# Power_Management.net
KiCad netlist of a schematic drawn in Altium Designer
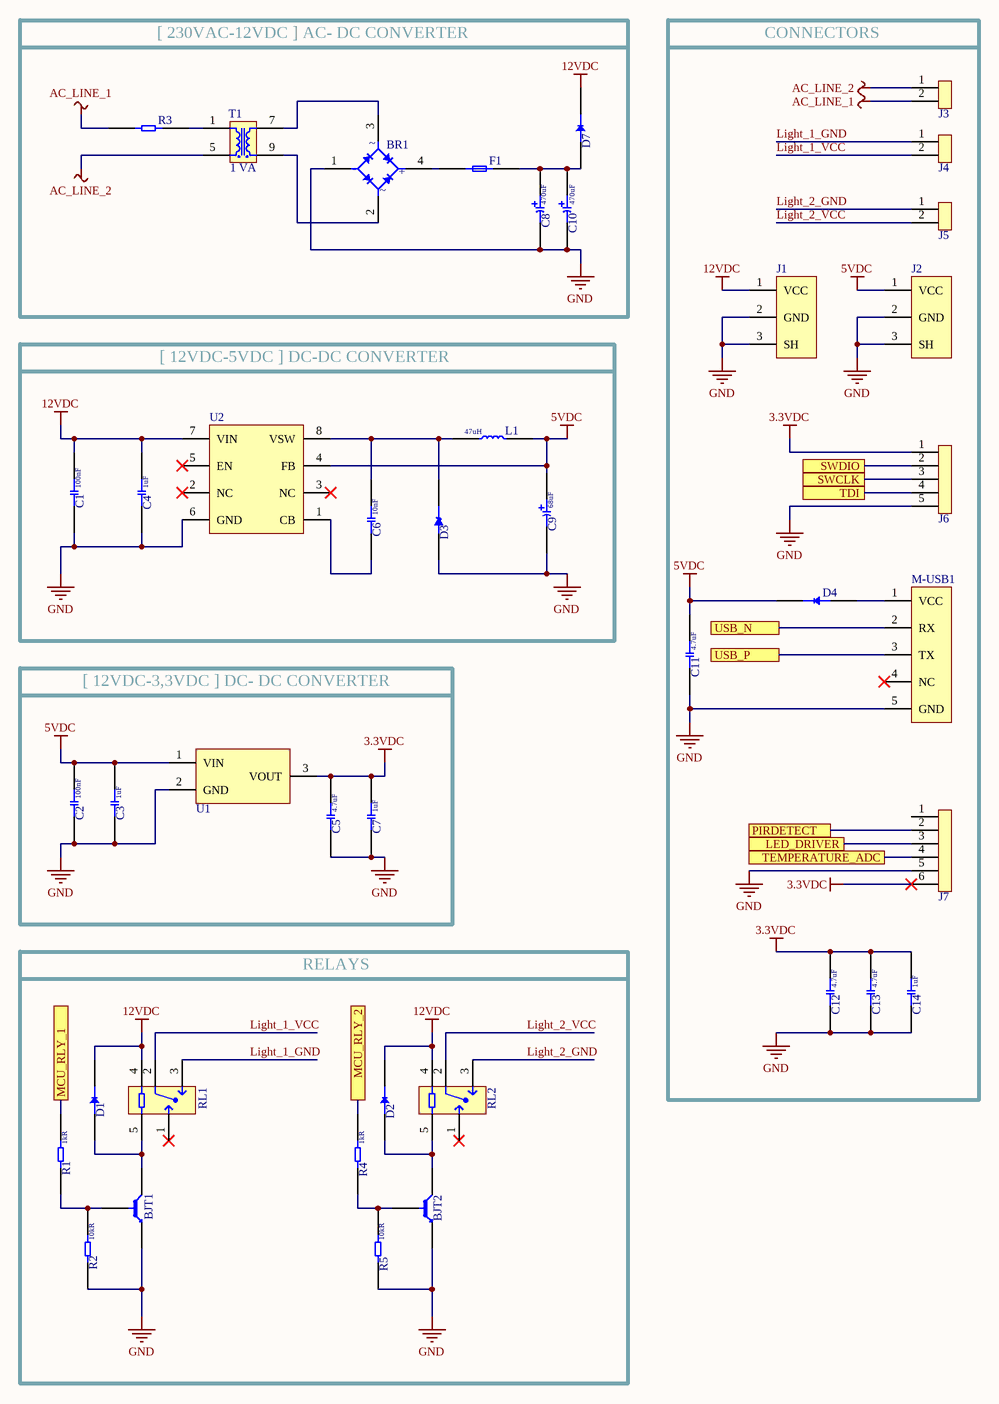
[diagram p0: Power Management.SchDoc]

(export (version "E")
  (design (tool "Eeschema 10.0.6"))
  (components
    (comp (ref "BJT1")
      (value "MMBT3904-7-F")
      (footprint "SOT-23F")
      (description "TRANS NPN 40V 0.2A SMD SOT23-3")
      (fields (field (name "MANUFACTURER") "Diodes Zetex") (field (name "DESIGNED BY") "M.C"))
      (libsource (lib "HedefPro_Library") (part "MMBT3904-7-F"))
    )
    (comp (ref "BJT2")
      (value "MMBT3904-7-F")
      (footprint "SOT-23F")
      (description "TRANS NPN 40V 0.2A SMD SOT23-3")
      (fields (field (name "MANUFACTURER") "Diodes Zetex") (field (name "DESIGNED BY") "M.C"))
      (libsource (lib "HedefPro_Library") (part "MMBT3904-7-F"))
    )
    (comp (ref "BR1")
      (value "DB105STR")
      (footprint "DB105STR")
      (description "BRIDGE RECT 1PHASE 600V 1A DB-S")
      (fields (field (name "MANUFACTURER") "Sangdest Microelectronics") (field (name "DESIGNED BY") "M.C"))
      (libsource (lib "HedefPro_Library") (part "DB105STR"))
    )
    (comp (ref "C1")
      (value "C0603C104K5RACTU")
      (footprint "CAP_0603")
      (description "Multilayer Ceramic Capacitors (MLCC) - SMD/SMT 50volts 0.1uF X7R 10%")
      (fields
        (field (name "MANUFACTURER") "KEMET")
        (field (name "TOLERANCE") "10%")
        (field (name "CAPACITANCE") "100nF")
        (field (name "DESIGNED BY") "M.C")
      )
      (libsource (lib "HedefPro_Library") (part "CAP 100nF 0603"))
    )
    (comp (ref "C2")
      (value "C0603C104K5RACTU")
      (footprint "CAP_0603")
      (description "Multilayer Ceramic Capacitors (MLCC) - SMD/SMT 50volts 0.1uF X7R 10%")
      (fields
        (field (name "MANUFACTURER") "KEMET")
        (field (name "TOLERANCE") "10%")
        (field (name "CAPACITANCE") "100nF")
        (field (name "DESIGNED BY") "M.C")
      )
      (libsource (lib "HedefPro_Library") (part "CAP 100nF 0603"))
    )
    (comp (ref "C3")
      (value "CL21B105KBFNNNE")
      (footprint "CAP_0805")
      (fields
        (field (name "MANUFACTURER") "Samsung")
        (field (name "TOLERANCE") "10%")
        (field (name "VOLTAGE") "50V")
        (field (name "CAPACITANCE") "1uF")
        (field (name "DESIGNED BY") "M.C")
      )
      (libsource (lib "HedefPro_Library") (part "CAP 1uF 0805"))
    )
    (comp (ref "C4")
      (value "CL21B105KBFNNNE")
      (footprint "CAP_0805")
      (fields
        (field (name "MANUFACTURER") "Samsung")
        (field (name "TOLERANCE") "10%")
        (field (name "VOLTAGE") "50V")
        (field (name "CAPACITANCE") "1uF")
        (field (name "DESIGNED BY") "M.C")
      )
      (libsource (lib "HedefPro_Library") (part "CAP 1uF 0805"))
    )
    (comp (ref "C5")
      (value "CL21A475KAQNNNE")
      (footprint "CAP_0805")
      (fields
        (field (name "MANUFACTURER") "Samsung")
        (field (name "TOLERANCE") "10%")
        (field (name "CAPACITANCE") "4.7uF")
        (field (name "DESIGNED BY") "M.C")
      )
      (libsource (lib "HedefPro_Library") (part "CAP 4.7uF 0805"))
    )
    (comp (ref "C6")
      (value "0603B103K500CT")
      (footprint "CAP_0603")
      (description "WALSIN - 0603B103K500CT - CAP, 0.01µF, 50V, 10%, X7R, 0603")
      (fields
        (field (name "MANUFACTURER") "Walsin Technologies")
        (field (name "TOLERANCE") "10%")
        (field (name "CAPACITANCE") "10nF")
        (field (name "DESIGNED BY") "M.C")
      )
      (libsource (lib "HedefPro_Library") (part "CAP 10nF 0603"))
    )
    (comp (ref "C7")
      (value "CL21B105KBFNNNE")
      (footprint "CAP_0805")
      (fields
        (field (name "MANUFACTURER") "Samsung")
        (field (name "TOLERANCE") "10%")
        (field (name "VOLTAGE") "50V")
        (field (name "CAPACITANCE") "1uF")
        (field (name "DESIGNED BY") "M.C")
      )
      (libsource (lib "HedefPro_Library") (part "CAP 1uF 0805"))
    )
    (comp (ref "C8")
      (value "ESH477M050AH4AA")
      (footprint "ESH477M050AH4AA")
      (description "Cap, 470UF, 50V, Alu Elec, Radial")
      (fields
        (field (name "MANUFACTURER") "KEMET")
        (field (name "TOLERANCE") "20%")
        (field (name "CAPACITANCE") "470uF")
        (field (name "DESIGNED BY") "M.C")
      )
      (libsource (lib "HedefPro_Library") (part "ESH477M050AH4AA"))
    )
    (comp (ref "C9")
      (value "EEV686M035A9HAA")
      (footprint "EEV686M035A9HAA")
      (description "Cap Aluminum Lytic 68uF 35V 20% (6.3 X 7.7mm) SMD 280mA 2000h 105C T/R")
      (fields
        (field (name "MANUFACTURER") "KEMET")
        (field (name "TOLERANCE") "20%")
        (field (name "CAPACITANCE") "68uF")
        (field (name "DESIGNED BY") "M.C")
      )
      (libsource (lib "HedefPro_Library") (part "EEV686M035A9HAA"))
    )
    (comp (ref "C10")
      (value "ESH477M050AH4AA")
      (footprint "ESH477M050AH4AA")
      (description "Cap, 470UF, 50V, Alu Elec, Radial")
      (fields
        (field (name "MANUFACTURER") "KEMET")
        (field (name "TOLERANCE") "20%")
        (field (name "CAPACITANCE") "470uF")
        (field (name "DESIGNED BY") "M.C")
      )
      (libsource (lib "HedefPro_Library") (part "ESH477M050AH4AA"))
    )
    (comp (ref "C11")
      (value "CL21A475KAQNNNE")
      (footprint "CAP_0805")
      (fields
        (field (name "MANUFACTURER") "Samsung")
        (field (name "TOLERANCE") "10%")
        (field (name "CAPACITANCE") "4.7uF")
        (field (name "DESIGNED BY") "M.C")
      )
      (libsource (lib "HedefPro_Library") (part "CAP 4.7uF 0805"))
    )
    (comp (ref "C12")
      (value "CL21A475KAQNNNE")
      (footprint "CAP_0805")
      (fields
        (field (name "MANUFACTURER") "Samsung")
        (field (name "TOLERANCE") "10%")
        (field (name "CAPACITANCE") "4.7uF")
        (field (name "DESIGNED BY") "M.C")
      )
      (libsource (lib "HedefPro_Library") (part "CAP 4.7uF 0805"))
    )
    (comp (ref "C13")
      (value "CL21A475KAQNNNE")
      (footprint "CAP_0805")
      (fields
        (field (name "MANUFACTURER") "Samsung")
        (field (name "TOLERANCE") "10%")
        (field (name "CAPACITANCE") "4.7uF")
        (field (name "DESIGNED BY") "M.C")
      )
      (libsource (lib "HedefPro_Library") (part "CAP 4.7uF 0805"))
    )
    (comp (ref "C14")
      (value "CL21B105KBFNNNE")
      (footprint "CAP_0805")
      (fields
        (field (name "MANUFACTURER") "Samsung")
        (field (name "TOLERANCE") "10%")
        (field (name "VOLTAGE") "50V")
        (field (name "CAPACITANCE") "1uF")
        (field (name "DESIGNED BY") "M.C")
      )
      (libsource (lib "HedefPro_Library") (part "CAP 1uF 0805"))
    )
    (comp (ref "D1")
      (value "1N4148WS")
      (footprint "SOD323F")
      (description "ON SEMICONDUCTOR - 1N4148WS - Small Signal Diode, Single, 75 V, 150 mA, 1 V, 4 ns")
      (fields (field (name "MANUFACTURER") "ON Semiconductor / Fairchild") (field (name "DESIGNED BY") "M.C"))
      (libsource (lib "HedefPro_Library") (part "1N4148WS"))
    )
    (comp (ref "D2")
      (value "1N4148WS")
      (footprint "SOD323F")
      (description "ON SEMICONDUCTOR - 1N4148WS - Small Signal Diode, Single, 75 V, 150 mA, 1 V, 4 ns")
      (fields (field (name "MANUFACTURER") "ON Semiconductor / Fairchild") (field (name "DESIGNED BY") "M.C"))
      (libsource (lib "HedefPro_Library") (part "1N4148WS"))
    )
    (comp (ref "D3")
      (value "1SMB5919BT3G")
      (footprint "SMB _CASE")
      (description "Diode Zener Single 5.6V 5% 3W 2-Pin SMB T/R")
      (fields
        (field (name "MANUFACTURER") "ON Semiconductor")
        (field (name "TOLERANCE") "5%")
        (field (name "DESIGNED BY") "M.C")
      )
      (libsource (lib "HedefPro_Library") (part "1SMB5919BT3G"))
    )
    (comp (ref "D4")
      (value "1N4148WS")
      (footprint "SOD323F")
      (description "ON SEMICONDUCTOR - 1N4148WS - Small Signal Diode, Single, 75 V, 150 mA, 1 V, 4 ns")
      (fields (field (name "MANUFACTURER") "ON Semiconductor / Fairchild") (field (name "DESIGNED BY") "M.C"))
      (libsource (lib "HedefPro_Library") (part "1N4148WS"))
    )
    (comp (ref "D7")
      (value "1N4148WS")
      (footprint "SOD323F")
      (description "ON SEMICONDUCTOR - 1N4148WS - Small Signal Diode, Single, 75 V, 150 mA, 1 V, 4 ns")
      (fields (field (name "MANUFACTURER") "ON Semiconductor / Fairchild") (field (name "DESIGNED BY") "M.C"))
      (libsource (lib "HedefPro_Library") (part "1N4148WS"))
    )
    (comp (ref "F1")
      (value "3413.0216.22")
      (footprint "1206(3216)")
      (description "FUSE BRD MNT 1A 32VAC 63VDC 1206")
      (fields (field (name "MANUFACTURER") "Schurter") (field (name "DESIGNED BY") "M.C"))
      (libsource (lib "HedefPro_Library") (part "3413.0216.22"))
    )
    (comp (ref "J1")
      (value "PJ-037AH-SMT-TR")
      (footprint "PJ-037AH-SMT-TR")
      (description "DC Power Connectors Power Jacks")
      (fields (field (name "MANUFACTURER") "CUI") (field (name "DESIGNED BY") "M.C"))
      (libsource (lib "HedefPro_Library") (part "PJ-037AH-SMT-TR"))
    )
    (comp (ref "J2")
      (value "PJ-037AH-SMT-TR")
      (footprint "PJ-037AH-SMT-TR")
      (description "DC Power Connectors Power Jacks")
      (fields (field (name "MANUFACTURER") "CUI") (field (name "DESIGNED BY") "M.C"))
      (libsource (lib "HedefPro_Library") (part "PJ-037AH-SMT-TR"))
    )
    (comp (ref "J3")
      (value "TBP01R1-508-02BE")
      (footprint "TBP01R1-508")
      (description "Conn Shrouded Header HDR 2 POS 5.08mm Solder RA Side Entry Thru-Hole Bag")
      (fields (field (name "MANUFACTURER") "CUI") (field (name "DESIGNED BY") "M.C"))
      (libsource (lib "HedefPro_Library") (part "TBP01R1-508-02BE"))
    )
    (comp (ref "J4")
      (value "TBP01R1-508-02BE")
      (footprint "TBP01R1-508")
      (description "Conn Shrouded Header HDR 2 POS 5.08mm Solder RA Side Entry Thru-Hole Bag")
      (fields (field (name "MANUFACTURER") "CUI") (field (name "DESIGNED BY") "M.C"))
      (libsource (lib "HedefPro_Library") (part "TBP01R1-508-02BE"))
    )
    (comp (ref "J5")
      (value "TBP01R1-508-02BE")
      (footprint "TBP01R1-508")
      (description "Conn Shrouded Header HDR 2 POS 5.08mm Solder RA Side Entry Thru-Hole Bag")
      (fields (field (name "MANUFACTURER") "CUI") (field (name "DESIGNED BY") "M.C"))
      (libsource (lib "HedefPro_Library") (part "TBP01R1-508-02BE"))
    )
    (comp (ref "J6")
      (value "SMH-105-02-L-S")
      (footprint "PINHEADER1X5_RA")
      (description ".100 C.L. HORIZONTAL SMT SOCKET")
      (fields (field (name "MANUFACTURER") "Samtec") (field (name "DESIGNED BY") "M.C"))
      (libsource (lib "HedefPro_Library") (part "SMH-105-02-L-S"))
    )
    (comp (ref "J7")
      (value "64800611622")
      (footprint "64800611622")
      (description "1.50mm 6PIN Connector")
      (fields (field (name "MANUFACTURER") "Wurth Electronics") (field (name "DESIGNED BY") "M.C"))
      (libsource (lib "HedefPro_Library") (part "64800611622"))
    )
    (comp (ref "L1")
      (value "78438335470")
      (footprint "IND_1212")
      (description "FIXED IND 47UH 390MA 2.3 OHM SMD")
      (fields
        (field (name "MANUFACTURER") "Wurth Electronics")
        (field (name "TOLERANCE") "30%")
        (field (name "INDUCTANCE") "47uH")
        (field (name "DESIGNED BY") "M.C")
      )
      (libsource (lib "HedefPro_Library") (part "78438335470"))
    )
    (comp (ref "M-USB1")
      (value "10118192-0001LF")
      (footprint "MICRO_B_USB")
      (description "CONN USB MICRO B RECPT SMT R/A")
      (fields (field (name "MANUFACTURER") "Amphenol ICC / FCI") (field (name "DESIGNED BY") "M.C"))
      (libsource (lib "HedefPro_Library") (part "USB MICRO"))
    )
    (comp (ref "R1")
      (value "RC0603FR-101KL")
      (footprint "RES_0603")
      (description "Res Thick Film 0603 1K Ohm 1% 0.1W(1/10W) ±100ppm/C Pad SMD T/R")
      (fields
        (field (name "MANUFACTURER") "Yageo")
        (field (name "TOLERANCE") "1%")
        (field (name "RESISTANCE") "1kR")
        (field (name "DESIGNED BY") "M.C")
      )
      (libsource (lib "HedefPro_Library") (part "RES 1kR OHM 0603"))
    )
    (comp (ref "R2")
      (value "RC0603FR-0710KL")
      (footprint "RES_0603")
      (description "Res General Purpose Thick Film 0603 10K Ohm 1% 1/10W ±100ppm/°C Molded SMD Paper T/R")
      (fields
        (field (name "MANUFACTURER") "Yageo")
        (field (name "TOLERANCE") "1%")
        (field (name "RESISTANCE") "10kR")
        (field (name "DESIGNED BY") "M.C")
      )
      (libsource (lib "HedefPro_Library") (part "RES 10kR OHM 0603"))
    )
    (comp (ref "R3")
      (value "5WD27")
      (footprint "RES_AXIAL_W")
      (description "Resistor 5 Watt Cermet Wirewound Flameproof .27 Ohm 5% Axial Lead")
      (fields
        (field (name "MANUFACTURER") "NTE Electronics")
        (field (name "TOLERANCE") "5%")
        (field (name "DESIGNED BY") "M.C")
      )
      (libsource (lib "HedefPro_Library") (part "5WD27"))
    )
    (comp (ref "R4")
      (value "RC0603FR-101KL")
      (footprint "RES_0603")
      (description "Res Thick Film 0603 1K Ohm 1% 0.1W(1/10W) ±100ppm/C Pad SMD T/R")
      (fields
        (field (name "MANUFACTURER") "Yageo")
        (field (name "TOLERANCE") "1%")
        (field (name "RESISTANCE") "1kR")
        (field (name "DESIGNED BY") "M.C")
      )
      (libsource (lib "HedefPro_Library") (part "RES 1kR OHM 0603"))
    )
    (comp (ref "R5")
      (value "RC0603FR-0710KL")
      (footprint "RES_0603")
      (description "Res General Purpose Thick Film 0603 10K Ohm 1% 1/10W ±100ppm/°C Molded SMD Paper T/R")
      (fields
        (field (name "MANUFACTURER") "Yageo")
        (field (name "TOLERANCE") "1%")
        (field (name "RESISTANCE") "10kR")
        (field (name "DESIGNED BY") "M.C")
      )
      (libsource (lib "HedefPro_Library") (part "RES 10kR OHM 0603"))
    )
    (comp (ref "RL1")
      (value "ALQ1F05")
      (footprint "ALQ1F05")
      (description "General Purpose Relay SPDT (1 Form C) 5VDC Coil Through Hole")
      (fields (field (name "MANUFACTURER") "Panasonic") (field (name "DESIGNED BY") "M.C"))
      (libsource (lib "HedefPro_Library") (part "ALQ1F05"))
    )
    (comp (ref "RL2")
      (value "ALQ1F05")
      (footprint "ALQ1F05")
      (description "General Purpose Relay SPDT (1 Form C) 5VDC Coil Through Hole")
      (fields (field (name "MANUFACTURER") "Panasonic") (field (name "DESIGNED BY") "M.C"))
      (libsource (lib "HedefPro_Library") (part "ALQ1F05"))
    )
    (comp (ref "T1")
      (value "BV302S12010-ZU")
      (footprint "BV302S")
      (description "230V- 12V Transformer 1VA")
      (fields
        (field (name "MANUFACTURER") "Zettler Magnetics")
        (field (name "RATED POWER") "1 VA")
        (field (name "DESIGNED BY") "M.C")
      )
      (libsource (lib "HedefPro_Library") (part "BV302S12010-ZU"))
    )
    (comp (ref "U1")
      (value "AP7361-33E-13")
      (footprint "SOT223")
      (description "LDO Regulator Pos 3.3V 1A 4-Pin(3+Tab) SOT-223 T/R")
      (fields (field (name "MANUFACTURER") "Diodes") (field (name "DESIGNED BY") "M.C"))
      (libsource (lib "HedefPro_Library") (part "AP7361-33E-13"))
    )
    (comp (ref "U2")
      (value "LM2675MX-12/NOPB")
      (footprint "SOIC8")
      (description "Switching Voltage Regulators Pwr Cnvtr Hi Eff 1A SD Vtg Reg")
      (fields (field (name "MANUFACTURER") "TI National Semiconductor") (field (name "DESIGNED BY") "M.C"))
      (libsource (lib "HedefPro_Library") (part "LM2675MX-12/NOPB"))
    )
  )
  (nets
    (net (code "1") (name "/LED_DRIVER") (class "Default")
      (node (ref "J7") (pin "3") (pinfunction "3_3") (pintype "passive"))
    )
    (net (code "2") (name "/Light_1_GND") (class "Default")
      (node (ref "J4") (pin "1") (pinfunction "1_1") (pintype "passive"))
      (node (ref "RL1") (pin "3") (pinfunction "3_3") (pintype "passive"))
    )
    (net (code "3") (name "/Light_1_VCC") (class "Default")
      (node (ref "J4") (pin "2") (pinfunction "2_2") (pintype "passive"))
      (node (ref "RL1") (pin "2") (pinfunction "2_2") (pintype "passive"))
    )
    (net (code "4") (name "/Light_2_GND") (class "Default")
      (node (ref "J5") (pin "1") (pinfunction "1_1") (pintype "passive"))
      (node (ref "RL2") (pin "3") (pinfunction "3_3") (pintype "passive"))
    )
    (net (code "5") (name "/Light_2_VCC") (class "Default")
      (node (ref "J5") (pin "2") (pinfunction "2_2") (pintype "passive"))
      (node (ref "RL2") (pin "2") (pinfunction "2_2") (pintype "passive"))
    )
    (net (code "6") (name "/MCU_RLY_1") (class "Default")
      (node (ref "R1") (pin "2") (pinfunction "2_2") (pintype "passive"))
    )
    (net (code "7") (name "/MCU_RLY_2") (class "Default")
      (node (ref "R4") (pin "2") (pinfunction "2_2") (pintype "passive"))
    )
    (net (code "8") (name "/PIRDETECT") (class "Default")
      (node (ref "J7") (pin "2") (pinfunction "2_2") (pintype "passive"))
    )
    (net (code "9") (name "/SWCLK") (class "Default")
      (node (ref "J6") (pin "3") (pinfunction "3_3") (pintype "passive"))
    )
    (net (code "10") (name "/SWDIO") (class "Default")
      (node (ref "J6") (pin "2") (pinfunction "2_2") (pintype "passive"))
    )
    (net (code "11") (name "/TDI") (class "Default")
      (node (ref "J6") (pin "4") (pinfunction "4_4") (pintype "passive"))
    )
    (net (code "12") (name "/TEMPERATURE_ADC") (class "Default")
      (node (ref "J7") (pin "4") (pinfunction "4_4") (pintype "passive"))
    )
    (net (code "13") (name "/USB_N") (class "Default")
      (node (ref "M-USB1") (pin "2") (pinfunction "RX_2") (pintype "passive"))
    )
    (net (code "14") (name "/USB_P") (class "Default")
      (node (ref "M-USB1") (pin "3") (pinfunction "TX_3") (pintype "passive"))
    )
    (net (code "15") (name "3.3VDC") (class "Default")
      (node (ref "C12") (pin "2") (pinfunction "2_2") (pintype "passive"))
      (node (ref "C13") (pin "2") (pinfunction "2_2") (pintype "passive"))
      (node (ref "C14") (pin "2") (pinfunction "2_2") (pintype "passive"))
      (node (ref "C5") (pin "2") (pinfunction "2_2") (pintype "passive"))
      (node (ref "C7") (pin "2") (pinfunction "2_2") (pintype "passive"))
      (node (ref "J6") (pin "1") (pinfunction "1_1") (pintype "passive"))
      (node (ref "J7") (pin "6") (pinfunction "6_6") (pintype "passive"))
      (node (ref "U1") (pin "3") (pinfunction "VOUT_3") (pintype "passive"))
    )
    (net (code "16") (name "5VDC") (class "Default")
      (node (ref "C11") (pin "2") (pinfunction "2_2") (pintype "passive"))
      (node (ref "C2") (pin "2") (pinfunction "2_2") (pintype "passive"))
      (node (ref "C3") (pin "2") (pinfunction "2_2") (pintype "passive"))
      (node (ref "C9") (pin "1") (pinfunction "1_1") (pintype "passive"))
      (node (ref "D4") (pin "1") (pinfunction "1_1") (pintype "passive"))
      (node (ref "J2") (pin "1") (pinfunction "VCC_1") (pintype "passive"))
      (node (ref "L1") (pin "2") (pinfunction "2_2") (pintype "passive"))
      (node (ref "U1") (pin "1") (pinfunction "VIN_1") (pintype "passive"))
      (node (ref "U2") (pin "4") (pinfunction "FB_4") (pintype "passive"))
    )
    (net (code "17") (name "12VDC") (class "Default")
      (node (ref "C1") (pin "2") (pinfunction "2_2") (pintype "passive"))
      (node (ref "C4") (pin "2") (pinfunction "2_2") (pintype "passive"))
      (node (ref "D1") (pin "1") (pinfunction "1_1") (pintype "passive"))
      (node (ref "D2") (pin "1") (pinfunction "1_1") (pintype "passive"))
      (node (ref "D7") (pin "1") (pinfunction "1_1") (pintype "passive"))
      (node (ref "J1") (pin "1") (pinfunction "VCC_1") (pintype "passive"))
      (node (ref "RL1") (pin "4") (pinfunction "4_4") (pintype "passive"))
      (node (ref "RL2") (pin "4") (pinfunction "4_4") (pintype "passive"))
      (node (ref "U2") (pin "7") (pinfunction "VIN_7") (pintype "passive"))
    )
    (net (code "18") (name "AC_LINE_1") (class "Default")
      (node (ref "J3") (pin "2") (pinfunction "2_2") (pintype "passive"))
      (node (ref "R3") (pin "1") (pinfunction "1_1") (pintype "passive"))
    )
    (net (code "19") (name "AC_LINE_2") (class "Default")
      (node (ref "J3") (pin "1") (pinfunction "1_1") (pintype "passive"))
      (node (ref "T1") (pin "5") (pinfunction "5_5") (pintype "passive"))
    )
    (net (code "20") (name "GND") (class "Default")
      (node (ref "BJT1") (pin "2") (pinfunction "E_2") (pintype "passive"))
      (node (ref "BJT2") (pin "2") (pinfunction "E_2") (pintype "passive"))
      (node (ref "BR1") (pin "1") (pinfunction "-_1") (pintype "passive"))
      (node (ref "C1") (pin "1") (pinfunction "1_1") (pintype "passive"))
      (node (ref "C10") (pin "2") (pinfunction "2_2") (pintype "passive"))
      (node (ref "C11") (pin "1") (pinfunction "1_1") (pintype "passive"))
      (node (ref "C12") (pin "1") (pinfunction "1_1") (pintype "passive"))
      (node (ref "C13") (pin "1") (pinfunction "1_1") (pintype "passive"))
      (node (ref "C14") (pin "1") (pinfunction "1_1") (pintype "passive"))
      (node (ref "C2") (pin "1") (pinfunction "1_1") (pintype "passive"))
      (node (ref "C3") (pin "1") (pinfunction "1_1") (pintype "passive"))
      (node (ref "C4") (pin "1") (pinfunction "1_1") (pintype "passive"))
      (node (ref "C5") (pin "1") (pinfunction "1_1") (pintype "passive"))
      (node (ref "C7") (pin "1") (pinfunction "1_1") (pintype "passive"))
      (node (ref "C8") (pin "2") (pinfunction "2_2") (pintype "passive"))
      (node (ref "C9") (pin "2") (pinfunction "2_2") (pintype "passive"))
      (node (ref "D3") (pin "2") (pinfunction "2_2") (pintype "passive"))
      (node (ref "J1") (pin "2") (pinfunction "GND_2") (pintype "passive"))
      (node (ref "J1") (pin "3") (pinfunction "SH_3") (pintype "passive"))
      (node (ref "J2") (pin "2") (pinfunction "GND_2") (pintype "passive"))
      (node (ref "J2") (pin "3") (pinfunction "SH_3") (pintype "passive"))
      (node (ref "J6") (pin "5") (pinfunction "5_5") (pintype "passive"))
      (node (ref "J7") (pin "5") (pinfunction "5_5") (pintype "passive"))
      (node (ref "M-USB1") (pin "5") (pinfunction "GND_5") (pintype "passive"))
      (node (ref "R2") (pin "1") (pinfunction "1_1") (pintype "passive"))
      (node (ref "R5") (pin "1") (pinfunction "1_1") (pintype "passive"))
      (node (ref "U1") (pin "2") (pinfunction "GND_2") (pintype "passive"))
      (node (ref "U2") (pin "6") (pinfunction "GND_6") (pintype "passive"))
    )
    (net (code "21") (name "Net-(BJT1-B)") (class "Default")
      (node (ref "BJT1") (pin "1") (pinfunction "B_1") (pintype "passive"))
      (node (ref "R1") (pin "1") (pinfunction "1_1") (pintype "passive"))
      (node (ref "R2") (pin "2") (pinfunction "2_2") (pintype "passive"))
    )
    (net (code "22") (name "Net-(BJT1-C)") (class "Default")
      (node (ref "BJT1") (pin "3") (pinfunction "C_3") (pintype "passive"))
      (node (ref "D1") (pin "2") (pinfunction "2_2") (pintype "passive"))
      (node (ref "RL1") (pin "5") (pinfunction "5_5") (pintype "passive"))
    )
    (net (code "23") (name "Net-(BJT2-B)") (class "Default")
      (node (ref "BJT2") (pin "1") (pinfunction "B_1") (pintype "passive"))
      (node (ref "R4") (pin "1") (pinfunction "1_1") (pintype "passive"))
      (node (ref "R5") (pin "2") (pinfunction "2_2") (pintype "passive"))
    )
    (net (code "24") (name "Net-(BJT2-C)") (class "Default")
      (node (ref "BJT2") (pin "3") (pinfunction "C_3") (pintype "passive"))
      (node (ref "D2") (pin "2") (pinfunction "2_2") (pintype "passive"))
      (node (ref "RL2") (pin "5") (pinfunction "5_5") (pintype "passive"))
    )
    (net (code "25") (name "Net-(BR1-+)") (class "Default")
      (node (ref "BR1") (pin "4") (pinfunction "+_4") (pintype "passive"))
      (node (ref "F1") (pin "1") (pinfunction "1_1") (pintype "passive"))
    )
    (net (code "26") (name "Net-(BR1-~-Pad2)") (class "Default")
      (node (ref "BR1") (pin "2") (pinfunction "~_2") (pintype "passive"))
      (node (ref "T1") (pin "9") (pinfunction "9_9") (pintype "passive"))
    )
    (net (code "27") (name "Net-(BR1-~-Pad3)") (class "Default")
      (node (ref "BR1") (pin "3") (pinfunction "~_3") (pintype "passive"))
      (node (ref "T1") (pin "7") (pinfunction "7_7") (pintype "passive"))
    )
    (net (code "28") (name "Net-(C10-Pad1)") (class "Default")
      (node (ref "C10") (pin "1") (pinfunction "1_1") (pintype "passive"))
      (node (ref "C8") (pin "1") (pinfunction "1_1") (pintype "passive"))
      (node (ref "D7") (pin "2") (pinfunction "2_2") (pintype "passive"))
      (node (ref "F1") (pin "2") (pinfunction "2_2") (pintype "passive"))
    )
    (net (code "29") (name "Net-(M-USB1-VCC)") (class "Default")
      (node (ref "D4") (pin "2") (pinfunction "2_2") (pintype "passive"))
      (node (ref "M-USB1") (pin "1") (pinfunction "VCC_1") (pintype "passive"))
    )
    (net (code "30") (name "Net-(R3-Pad2)") (class "Default")
      (node (ref "R3") (pin "2") (pinfunction "2_2") (pintype "passive"))
      (node (ref "T1") (pin "1") (pinfunction "1_1") (pintype "passive"))
    )
    (net (code "31") (name "Net-(U2-CB)") (class "Default")
      (node (ref "C6") (pin "1") (pinfunction "1_1") (pintype "passive"))
      (node (ref "U2") (pin "1") (pinfunction "CB_1") (pintype "passive"))
    )
    (net (code "32") (name "Net-(U2-VSW)") (class "Default")
      (node (ref "C6") (pin "2") (pinfunction "2_2") (pintype "passive"))
      (node (ref "D3") (pin "1") (pinfunction "1_1") (pintype "passive"))
      (node (ref "L1") (pin "1") (pinfunction "1_1") (pintype "passive"))
      (node (ref "U2") (pin "8") (pinfunction "VSW_8") (pintype "passive"))
    )
    (net (code "33") (name "unconnected-(J7-Pad1)") (class "Default")
      (node (ref "J7") (pin "1") (pinfunction "1_1") (pintype "passive"))
    )
    (net (code "34") (name "unconnected-(M-USB1-NC-Pad4)") (class "Default")
      (node (ref "M-USB1") (pin "4") (pinfunction "NC_4") (pintype "passive+no_connect"))
    )
    (net (code "35") (name "unconnected-(RL1-Pad1)") (class "Default")
      (node (ref "RL1") (pin "1") (pinfunction "1_1") (pintype "passive+no_connect"))
    )
    (net (code "36") (name "unconnected-(RL2-Pad1)") (class "Default")
      (node (ref "RL2") (pin "1") (pinfunction "1_1") (pintype "passive+no_connect"))
    )
    (net (code "37") (name "unconnected-(U2-EN-Pad5)") (class "Default")
      (node (ref "U2") (pin "5") (pinfunction "EN_5") (pintype "passive+no_connect"))
    )
    (net (code "38") (name "unconnected-(U2-NC-Pad2)") (class "Default")
      (node (ref "U2") (pin "2") (pinfunction "NC_2") (pintype "passive+no_connect"))
    )
    (net (code "39") (name "unconnected-(U2-NC-Pad3)") (class "Default")
      (node (ref "U2") (pin "3") (pinfunction "NC_3") (pintype "passive+no_connect"))
    )
  )
)
